# STC15_U1.net
KiCad netlist of a schematic drawn in Altium Designer
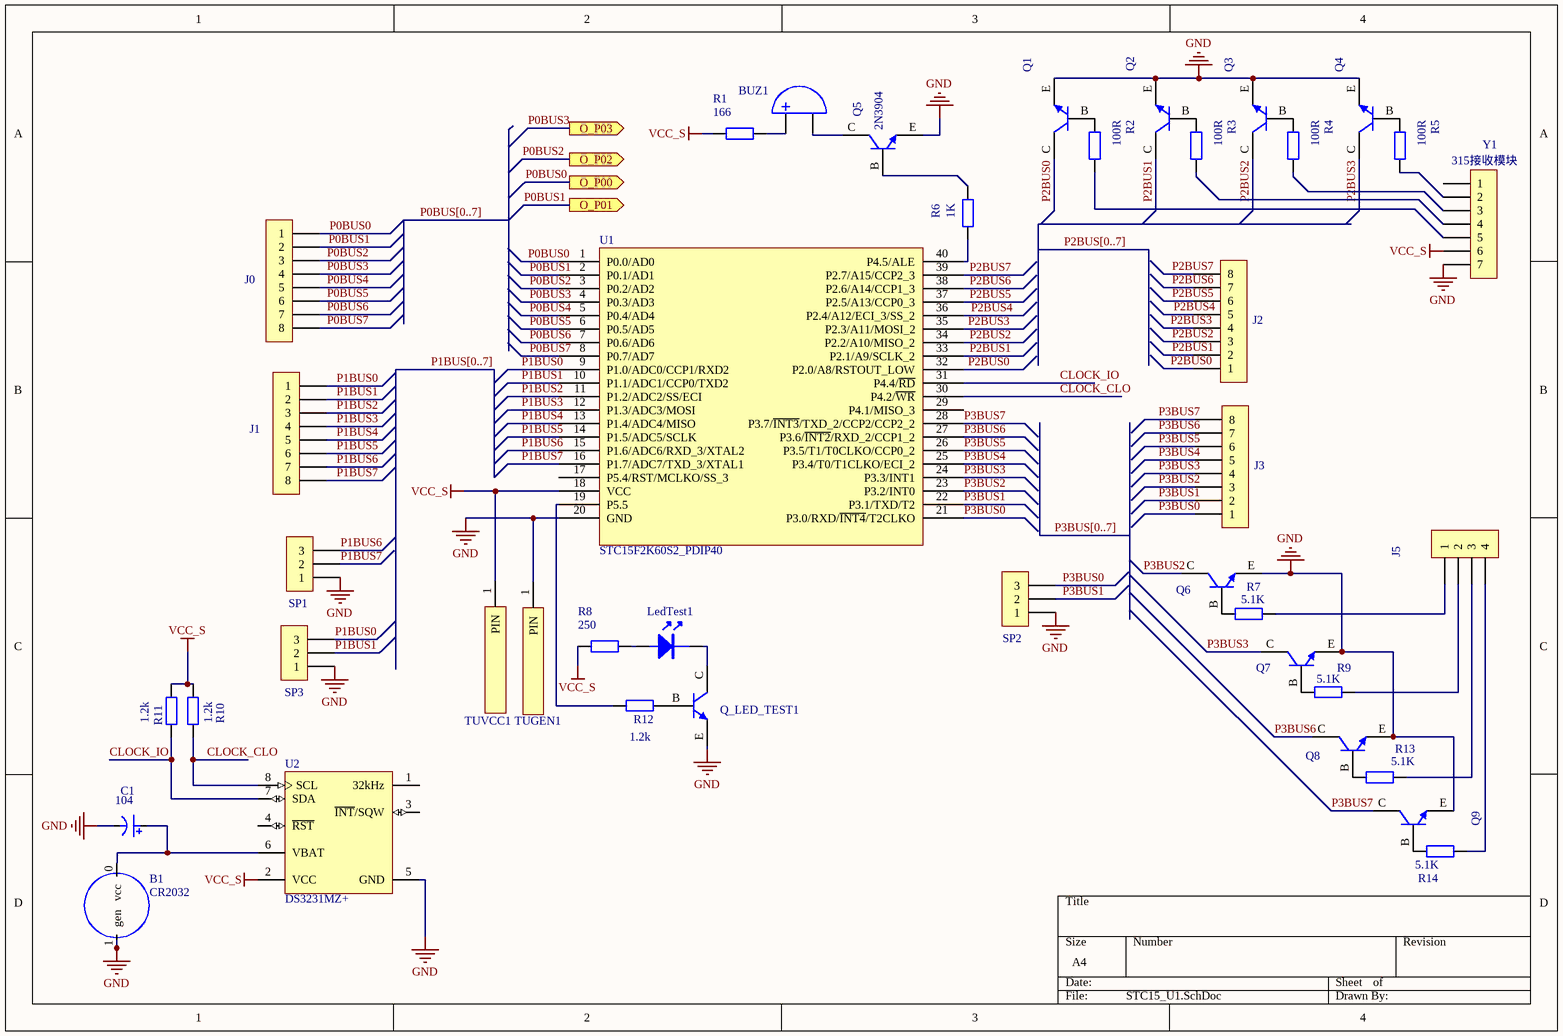
[diagram p0: STC15_U1.SchDoc]

(export (version "E")
  (design (tool "Eeschema 10.0.6"))
  (components
    (comp (ref "B1") (value "CR2032") (footprint "CR2032座") (libsource (lib "KF接口") (part "CR2032")))
    (comp (ref "BUZ1")
      (value "SD1209T5-A1")
      (footprint "BUZ5-12-0R5-9MM")
      (description "DIP,12x9mm,额定电压DC5V,频率2048Hz,黑色,间距5mm")
      (fields
        (field (name "PART NUMBER") "102BA-00004OD.01")
        (field (name "ALLOW ALTENATIVE PART") "Y")
        (field (name "REMARK") "Verified by BU1（黄雄青） check list V1.0")
        (field (name "MODIFY TIME") "2016年05月12号")
        (field (name "APPROVED") "YES")
      )
      (libsource (lib "IA-04") (part "Buzzer-2-P1"))
    )
    (comp (ref "C1")
      (value "104")
      (footprint "CE5-6R5X5-1mm")
      (description "DIP,电容量681pf,额定电压2000V,偏差±10%,6.5X5mm")
      (fields
        (field (name "PART NUMBER") "102CB-00002OD.01")
        (field (name "ALLOW ALTENATIVE PART") "Y")
        (field (name "REMARK") "Verified by BU1（黄雄青） check list V1.0")
        (field (name "MODIFY TIME") "2015年11月05号")
        (field (name "APPROVED") "YES")
      )
      (libsource (lib "IA-04") (part "CAP_Alum-2-N2"))
    )
    (comp (ref "J0")
      (value "W7810811120AB")
      (footprint "XH8P-2R54-TH")
      (description "DIP,座子,封装脚距2.54mm,180度,1x8PIN,塑高/针长7.0/3.40mm,白色")
      (fields
        (field (name "PART NUMBER") "102NB-00026CY.01")
        (field (name "ALLOW ALTENATIVE PART") "Y")
        (field (name "REMARK") "Verified by CRD（赖程奇） check list V1.0")
        (field (name "MODIFY TIME") "2016年08月22号")
        (field (name "APPROVED") "YES")
      )
      (libsource (lib "IA-04") (part "J-8-NP"))
    )
    (comp (ref "J1")
      (value "W7810811120AB")
      (footprint "XH8P-2R54-TH")
      (description "DIP,座子,封装脚距2.54mm,180度,1x8PIN,塑高/针长7.0/3.40mm,白色")
      (fields
        (field (name "PART NUMBER") "102NB-00026CY.01")
        (field (name "ALLOW ALTENATIVE PART") "Y")
        (field (name "REMARK") "Verified by CRD（赖程奇） check list V1.0")
        (field (name "MODIFY TIME") "2016年08月22号")
        (field (name "APPROVED") "YES")
      )
      (libsource (lib "IA-04") (part "J-8-NP"))
    )
    (comp (ref "J2")
      (value "W7810811120AB")
      (footprint "XH8P-2R54-TH")
      (description "DIP,座子,封装脚距2.54mm,180度,1x8PIN,塑高/针长7.0/3.40mm,白色")
      (fields
        (field (name "PART NUMBER") "102NB-00026CY.01")
        (field (name "ALLOW ALTENATIVE PART") "Y")
        (field (name "REMARK") "Verified by CRD（赖程奇） check list V1.0")
        (field (name "MODIFY TIME") "2016年08月22号")
        (field (name "APPROVED") "YES")
      )
      (libsource (lib "") (part "J-8-NP_1"))
    )
    (comp (ref "J3")
      (value "W7810811120AB")
      (footprint "XH8P-2R54-TH")
      (description "DIP,座子,封装脚距2.54mm,180度,1x8PIN,塑高/针长7.0/3.40mm,白色")
      (fields
        (field (name "PART NUMBER") "102NB-00026CY.01")
        (field (name "ALLOW ALTENATIVE PART") "Y")
        (field (name "REMARK") "Verified by CRD（赖程奇） check list V1.0")
        (field (name "MODIFY TIME") "2016年08月22号")
        (field (name "APPROVED") "YES")
      )
      (libsource (lib "") (part "J-8-NP_1"))
    )
    (comp (ref "J5")
      (value "W7810411120AB")
      (footprint "XH4P-2R54-TH")
      (description "DIP,座子,封装脚距2.54mm,180度,1x4PIN,塑高/针长7.0/3.40mm,白色")
      (fields
        (field (name "PART NUMBER") "102NB-00025CY.01")
        (field (name "ALLOW ALTENATIVE PART") "Y")
        (field (name "REMARK") "Verified by CRD（赖程奇） check list V1.0")
        (field (name "MODIFY TIME") "2016年05月12号")
        (field (name "APPROVED") "YES")
      )
      (libsource (lib "IA-04") (part "J-4-NP"))
    )
    (comp (ref "LedTest1")
      (value "333-2SUBD/S400-A4")
      (footprint "LED2-D5X5")
      (description "DIP,封装/间距直径5/2.54mm,额定电压3.3V,亮度高亮,蓝色")
      (fields
        (field (name "PART NUMBER") "102DL-00029CH.01")
        (field (name "ALLOW ALTENATIVE PART") "Y")
        (field (name "REMARK") "Verified by CRD（张宗良） check list V1.0")
        (field (name "MODIFY TIME") "2017年01月07号")
        (field (name "APPROVED") "YES")
      )
      (libsource (lib "IA-04") (part "Diode-LED-2-N2"))
    )
    (comp (ref "Q1")
      (value "2N3904")
      (footprint "Triode:TO-92-3-EBC")
      (description "DIP,封装形式TO-92-3,耐压值40V,额定电流200mA,耗散功率625mW")
      (fields
        (field (name "PART NUMBER") "102GN-00009BA.01")
        (field (name "ALLOW ALTENATIVE PART") "Y")
        (field (name "REMARK") "Verified by BU1（吴明徽）check list V1.0")
        (field (name "MODIFY TIME") "2015年08月08号")
        (field (name "APPROVED") "YES")
      )
      (libsource (lib "IA-04") (part "Triode-NPN-BCE"))
    )
    (comp (ref "Q2")
      (value "2N3904")
      (footprint "Triode:TO-92-3-EBC")
      (description "DIP,封装形式TO-92-3,耐压值40V,额定电流200mA,耗散功率625mW")
      (fields
        (field (name "PART NUMBER") "102GN-00009BA.01")
        (field (name "ALLOW ALTENATIVE PART") "Y")
        (field (name "REMARK") "Verified by BU1（吴明徽）check list V1.0")
        (field (name "MODIFY TIME") "2015年08月08号")
        (field (name "APPROVED") "YES")
      )
      (libsource (lib "IA-04") (part "Triode-NPN-BCE"))
    )
    (comp (ref "Q3")
      (value "2N3904")
      (footprint "Triode:TO-92-3-EBC")
      (description "DIP,封装形式TO-92-3,耐压值40V,额定电流200mA,耗散功率625mW")
      (fields
        (field (name "PART NUMBER") "102GN-00009BA.01")
        (field (name "ALLOW ALTENATIVE PART") "Y")
        (field (name "REMARK") "Verified by BU1（吴明徽）check list V1.0")
        (field (name "MODIFY TIME") "2015年08月08号")
        (field (name "APPROVED") "YES")
      )
      (libsource (lib "IA-04") (part "Triode-NPN-BCE"))
    )
    (comp (ref "Q4")
      (value "2N3904")
      (footprint "Triode:TO-92-3-EBC")
      (description "DIP,封装形式TO-92-3,耐压值40V,额定电流200mA,耗散功率625mW")
      (fields
        (field (name "PART NUMBER") "102GN-00009BA.01")
        (field (name "ALLOW ALTENATIVE PART") "Y")
        (field (name "REMARK") "Verified by BU1（吴明徽）check list V1.0")
        (field (name "MODIFY TIME") "2015年08月08号")
        (field (name "APPROVED") "YES")
      )
      (libsource (lib "IA-04") (part "Triode-NPN-BCE"))
    )
    (comp (ref "Q5")
      (value "2N3904")
      (footprint "Triode:TO-92-3-EBC")
      (description "DIP,封装形式TO-92-3,耐压值40V,额定电流200mA,耗散功率625mW")
      (fields
        (field (name "PART NUMBER") "102GN-00009BA.01")
        (field (name "ALLOW ALTENATIVE PART") "Y")
        (field (name "REMARK") "Verified by BU1（吴明徽）check list V1.0")
        (field (name "MODIFY TIME") "2015年08月08号")
        (field (name "APPROVED") "YES")
      )
      (libsource (lib "IA-04") (part "Triode-NPN-BCE"))
    )
    (comp (ref "Q6")
      (value "2N3904")
      (footprint "Triode:TO-92-3-EBC")
      (description "DIP,封装形式TO-92-3,耐压值40V,额定电流200mA,耗散功率625mW")
      (fields
        (field (name "PART NUMBER") "102GN-00009BA.01")
        (field (name "ALLOW ALTENATIVE PART") "Y")
        (field (name "REMARK") "Verified by BU1（吴明徽）check list V1.0")
        (field (name "MODIFY TIME") "2015年08月08号")
        (field (name "APPROVED") "YES")
      )
      (libsource (lib "IA-04") (part "Triode-NPN-BCE"))
    )
    (comp (ref "Q7")
      (value "2N3904")
      (footprint "Triode:TO-92-3-EBC")
      (description "DIP,封装形式TO-92-3,耐压值40V,额定电流200mA,耗散功率625mW")
      (fields
        (field (name "PART NUMBER") "102GN-00009BA.01")
        (field (name "ALLOW ALTENATIVE PART") "Y")
        (field (name "REMARK") "Verified by BU1（吴明徽）check list V1.0")
        (field (name "MODIFY TIME") "2015年08月08号")
        (field (name "APPROVED") "YES")
      )
      (libsource (lib "IA-04") (part "Triode-NPN-BCE"))
    )
    (comp (ref "Q8")
      (value "2N3904")
      (footprint "Triode:TO-92-3-EBC")
      (description "DIP,封装形式TO-92-3,耐压值40V,额定电流200mA,耗散功率625mW")
      (fields
        (field (name "PART NUMBER") "102GN-00009BA.01")
        (field (name "ALLOW ALTENATIVE PART") "Y")
        (field (name "REMARK") "Verified by BU1（吴明徽）check list V1.0")
        (field (name "MODIFY TIME") "2015年08月08号")
        (field (name "APPROVED") "YES")
      )
      (libsource (lib "IA-04") (part "Triode-NPN-BCE"))
    )
    (comp (ref "Q9")
      (value "2N3904")
      (footprint "Triode:TO-92-3-EBC")
      (description "DIP,封装形式TO-92-3,耐压值40V,额定电流200mA,耗散功率625mW")
      (fields
        (field (name "PART NUMBER") "102GN-00009BA.01")
        (field (name "ALLOW ALTENATIVE PART") "Y")
        (field (name "REMARK") "Verified by BU1（吴明徽）check list V1.0")
        (field (name "MODIFY TIME") "2015年08月08号")
        (field (name "APPROVED") "YES")
      )
      (libsource (lib "IA-04") (part "Triode-NPN-BCE"))
    )
    (comp (ref "Q_LED_TEST1")
      (value "2N3904")
      (footprint "Triode:TO-92-3-EBC")
      (description "DIP,封装形式TO-92-3,耐压值40V,额定电流200mA,耗散功率625mW")
      (fields
        (field (name "PART NUMBER") "102GN-00009BA.01")
        (field (name "ALLOW ALTENATIVE PART") "Y")
        (field (name "REMARK") "Verified by BU1（吴明徽）check list V1.0")
        (field (name "MODIFY TIME") "2015年08月08号")
        (field (name "APPROVED") "YES")
      )
      (libsource (lib "IA-04") (part "Triode-NPN-BCE"))
    )
    (comp (ref "R1")
      (value "166")
      (footprint "RY0R25W")
      (description "DIP,阻值1K,精度±5%,9.0x3.3mm,额定功率1/2W")
      (fields
        (field (name "PART NUMBER") "102RO-00079BW.01")
        (field (name "ALLOW ALTENATIVE PART") "Y")
        (field (name "REMARK") "Verified by BU3（吴明徽）check list V1.0")
        (field (name "MODIFY TIME") "2015年07月10号")
        (field (name "APPROVED") "YES")
      )
      (libsource (lib "") (part "RES-2-NP_1"))
    )
    (comp (ref "R2")
      (value "100R")
      (footprint "RY0R25W")
      (description "DIP,阻值100R,精度±1%,6.1x2.29mm,额定功率1/4W")
      (fields
        (field (name "PART NUMBER") "102RO-00040BS.01")
        (field (name "ALLOW ALTENATIVE PART") "Y")
        (field (name "REMARK") "Verified by BU3（吴明徽）check list V1.0")
        (field (name "MODIFY TIME") "2015年07月10号")
        (field (name "APPROVED") "YES")
      )
      (libsource (lib "IA-04") (part "RES-2-NP"))
    )
    (comp (ref "R3")
      (value "100R")
      (footprint "RY0R25W")
      (description "DIP,阻值100R,精度±1%,6.1x2.29mm,额定功率1/4W")
      (fields
        (field (name "PART NUMBER") "102RO-00040BS.01")
        (field (name "ALLOW ALTENATIVE PART") "Y")
        (field (name "REMARK") "Verified by BU3（吴明徽）check list V1.0")
        (field (name "MODIFY TIME") "2015年07月10号")
        (field (name "APPROVED") "YES")
      )
      (libsource (lib "IA-04") (part "RES-2-NP"))
    )
    (comp (ref "R4")
      (value "100R")
      (footprint "RY0R25W")
      (description "DIP,阻值100R,精度±1%,6.1x2.29mm,额定功率1/4W")
      (fields
        (field (name "PART NUMBER") "102RO-00040BS.01")
        (field (name "ALLOW ALTENATIVE PART") "Y")
        (field (name "REMARK") "Verified by BU3（吴明徽）check list V1.0")
        (field (name "MODIFY TIME") "2015年07月10号")
        (field (name "APPROVED") "YES")
      )
      (libsource (lib "IA-04") (part "RES-2-NP"))
    )
    (comp (ref "R5")
      (value "100R")
      (footprint "RY0R25W")
      (description "DIP,阻值100R,精度±1%,6.1x2.29mm,额定功率1/4W")
      (fields
        (field (name "PART NUMBER") "102RO-00040BS.01")
        (field (name "ALLOW ALTENATIVE PART") "Y")
        (field (name "REMARK") "Verified by BU3（吴明徽）check list V1.0")
        (field (name "MODIFY TIME") "2015年07月10号")
        (field (name "APPROVED") "YES")
      )
      (libsource (lib "IA-04") (part "RES-2-NP"))
    )
    (comp (ref "R6")
      (value "1K")
      (footprint "RY0R25W")
      (description "DIP,阻值1K,精度±5%,9.0x3.3mm,额定功率1/2W")
      (fields
        (field (name "PART NUMBER") "102RO-00079BW.01")
        (field (name "ALLOW ALTENATIVE PART") "Y")
        (field (name "REMARK") "Verified by BU3（吴明徽）check list V1.0")
        (field (name "MODIFY TIME") "2015年07月10号")
        (field (name "APPROVED") "YES")
      )
      (libsource (lib "") (part "RES-2-NP_2"))
    )
    (comp (ref "R7")
      (value "5.1K")
      (footprint "RY0R25W")
      (description "DIP,阻值5.1K,精度±1%,6.2x2.29mm,额定功率1/4W")
      (fields
        (field (name "PART NUMBER") "102RO-00048BS.01")
        (field (name "ALLOW ALTENATIVE PART") "Y")
        (field (name "REMARK") "Verified by BU3（吴明徽）check list V1.0")
        (field (name "MODIFY TIME") "2015年07月10号")
        (field (name "APPROVED") "YES")
      )
      (libsource (lib "") (part "RES-2-NP_1"))
    )
    (comp (ref "R8")
      (value "250")
      (footprint "RY0R25W")
      (description "DIP,阻值8.2R,精度±1%,AXIAL0.4,额定功率1/2W")
      (fields
        (field (name "PART NUMBER") "102RO-00036BS.01")
        (field (name "ALLOW ALTENATIVE PART") "Y")
        (field (name "REMARK") "Verified by BU3（吴明徽）check list V1.0")
        (field (name "MODIFY TIME") "2015年07月10号")
        (field (name "APPROVED") "YES")
      )
      (libsource (lib "") (part "RES-2-NP_1"))
    )
    (comp (ref "R9")
      (value "5.1K")
      (footprint "RY0R25W")
      (description "DIP,阻值5.1K,精度±1%,6.2x2.29mm,额定功率1/4W")
      (fields
        (field (name "PART NUMBER") "102RO-00048BS.01")
        (field (name "ALLOW ALTENATIVE PART") "Y")
        (field (name "REMARK") "Verified by BU3（吴明徽）check list V1.0")
        (field (name "MODIFY TIME") "2015年07月10号")
        (field (name "APPROVED") "YES")
      )
      (libsource (lib "") (part "RES-2-NP_1"))
    )
    (comp (ref "R10")
      (value "1.2k")
      (footprint "RY0R25W")
      (description "DIP,阻值8.2R,精度±1%,AXIAL0.4,额定功率1/2W")
      (fields
        (field (name "PART NUMBER") "102RO-00036BS.01")
        (field (name "ALLOW ALTENATIVE PART") "Y")
        (field (name "REMARK") "Verified by BU3（吴明徽）check list V1.0")
        (field (name "MODIFY TIME") "2015年07月10号")
        (field (name "APPROVED") "YES")
      )
      (libsource (lib "IA-04") (part "RES-2-NP"))
    )
    (comp (ref "R11")
      (value "1.2k")
      (footprint "RY0R25W")
      (description "DIP,阻值8.2R,精度±1%,AXIAL0.4,额定功率1/2W")
      (fields
        (field (name "PART NUMBER") "102RO-00036BS.01")
        (field (name "ALLOW ALTENATIVE PART") "Y")
        (field (name "REMARK") "Verified by BU3（吴明徽）check list V1.0")
        (field (name "MODIFY TIME") "2015年07月10号")
        (field (name "APPROVED") "YES")
      )
      (libsource (lib "IA-04") (part "RES-2-NP"))
    )
    (comp (ref "R12")
      (value "1.2k")
      (footprint "RY0R25W")
      (description "DIP,阻值8.2R,精度±1%,AXIAL0.4,额定功率1/2W")
      (fields
        (field (name "PART NUMBER") "102RO-00036BS.01")
        (field (name "ALLOW ALTENATIVE PART") "Y")
        (field (name "REMARK") "Verified by BU3（吴明徽）check list V1.0")
        (field (name "MODIFY TIME") "2015年07月10号")
        (field (name "APPROVED") "YES")
      )
      (libsource (lib "") (part "RES-2-NP_1"))
    )
    (comp (ref "R13")
      (value "5.1K")
      (footprint "RY0R25W")
      (description "DIP,阻值5.1K,精度±1%,6.2x2.29mm,额定功率1/4W")
      (fields
        (field (name "PART NUMBER") "102RO-00048BS.01")
        (field (name "ALLOW ALTENATIVE PART") "Y")
        (field (name "REMARK") "Verified by BU3（吴明徽）check list V1.0")
        (field (name "MODIFY TIME") "2015年07月10号")
        (field (name "APPROVED") "YES")
      )
      (libsource (lib "") (part "RES-2-NP_1"))
    )
    (comp (ref "R14")
      (value "5.1K")
      (footprint "RY0R25W")
      (description "DIP,阻值5.1K,精度±1%,6.2x2.29mm,额定功率1/4W")
      (fields
        (field (name "PART NUMBER") "102RO-00048BS.01")
        (field (name "ALLOW ALTENATIVE PART") "Y")
        (field (name "REMARK") "Verified by BU3（吴明徽）check list V1.0")
        (field (name "MODIFY TIME") "2015年07月10号")
        (field (name "APPROVED") "YES")
      )
      (libsource (lib "") (part "RES-2-NP_1"))
    )
    (comp (ref "SP1")
      (value "~")
      (footprint "XH3P-2R54-TH")
      (description "DIP,座子,封装脚距2.54mm,180度,1x3PIN,塑高/针长7.0/3.40mm,白色")
      (fields
        (field (name "PART NUMBER") "102NB-00017CY.01")
        (field (name "ALLOW ALTENATIVE PART") "Y")
        (field (name "REMARK") "Verified by CRD（赖程奇） check list V1.0")
        (field (name "MODIFY TIME") "2015年11月06号")
        (field (name "APPROVED") "YES")
      )
      (libsource (lib "IA-04") (part "J-3-NP"))
    )
    (comp (ref "SP2")
      (value "~")
      (footprint "XH3P-2R54-TH")
      (description "DIP,座子,封装脚距2.54mm,180度,1x3PIN,塑高/针长7.0/3.40mm,白色")
      (fields
        (field (name "PART NUMBER") "102NB-00017CY.01")
        (field (name "ALLOW ALTENATIVE PART") "Y")
        (field (name "REMARK") "Verified by CRD（赖程奇） check list V1.0")
        (field (name "MODIFY TIME") "2015年11月06号")
        (field (name "APPROVED") "YES")
      )
      (libsource (lib "IA-04") (part "J-3-NP"))
    )
    (comp (ref "SP3")
      (value "~")
      (footprint "XH3P-2R54-TH")
      (description "DIP,座子,封装脚距2.54mm,180度,1x3PIN,塑高/针长7.0/3.40mm,白色")
      (fields
        (field (name "PART NUMBER") "102NB-00017CY.01")
        (field (name "ALLOW ALTENATIVE PART") "Y")
        (field (name "REMARK") "Verified by CRD（赖程奇） check list V1.0")
        (field (name "MODIFY TIME") "2015年11月06号")
        (field (name "APPROVED") "YES")
      )
      (libsource (lib "IA-04") (part "J-3-NP"))
    )
    (comp (ref "TUGEN1")
      (value "T？")
      (footprint "铺铜条")
      (description "2mm*20的铜条用于焊接")
      (libsource (lib "KF接口") (part "铺铜条"))
    )
    (comp (ref "TUVCC1")
      (value "T？")
      (footprint "铺铜条")
      (description "2mm*20的铜条用于焊接")
      (libsource (lib "KF接口") (part "铺铜条"))
    )
    (comp (ref "U1")
      (value "STC15F2K60S2_PDIP40")
      (footprint "DIP40")
      (libsource (lib "stcmcu_altium1819") (part "STC15F2K60S2_PDIP40"))
    )
    (comp (ref "U2")
      (value "DS3231MZ+")
      (footprint "S8MK+1_L")
      (description "+/-5ppm, MEMS based Real-Time Clock, I2C Interface, 8-Pin SO, -40 to 85 degC, Pb-Free")
      (libsource (lib "Maxim Real-Time Clocks (RTCs)") (part "DS3231MZ+"))
    )
    (comp (ref "Y1")
      (value "315接收模块")
      (footprint "CON7P-2R54-TH")
      (description "DIP,封装脚距2.54mm,180度,1x7PIN,黑色")
      (fields
        (field (name "PART NUMBER") "102NL-00032BV.01")
        (field (name "ALLOW ALTENATIVE PART") "Y")
        (field (name "REMARK") "Verified by CRD（赖程奇） check list V1.0")
        (field (name "MODIFY TIME") "2015年07月10号")
        (field (name "APPROVED") "YES")
      )
      (libsource (lib "IA-04") (part "CON7-NP"))
    )
  )
  (nets
    (net (code "1") (name "/CLOCK_CLO") (class "Default")
      (node (ref "R10") (pin "2") (pinfunction "2_2") (pintype "passive"))
      (node (ref "U1") (pin "30") (pinfunction "P4.2/~{WR}_30") (pintype "passive"))
      (node (ref "U2") (pin "8") (pinfunction "SCL_8") (pintype "input"))
    )
    (net (code "2") (name "/CLOCK_IO") (class "Default")
      (node (ref "R11") (pin "2") (pinfunction "2_2") (pintype "passive"))
      (node (ref "U1") (pin "31") (pinfunction "P4.4/~{RD}_31") (pintype "passive"))
      (node (ref "U2") (pin "7") (pinfunction "SDA_7") (pintype "bidirectional"))
    )
    (net (code "3") (name "/P0BUS0") (class "Default")
      (node (ref "J0") (pin "1") (pinfunction "1_1") (pintype "passive"))
      (node (ref "U1") (pin "1") (pinfunction "P0.0/AD0_1") (pintype "passive"))
    )
    (net (code "4") (name "/P0BUS1") (class "Default")
      (node (ref "J0") (pin "2") (pinfunction "2_2") (pintype "passive"))
      (node (ref "U1") (pin "2") (pinfunction "P0.1/AD1_2") (pintype "passive"))
    )
    (net (code "5") (name "/P0BUS2") (class "Default")
      (node (ref "J0") (pin "3") (pinfunction "3_3") (pintype "passive"))
      (node (ref "U1") (pin "3") (pinfunction "P0.2/AD2_3") (pintype "passive"))
    )
    (net (code "6") (name "/P0BUS3") (class "Default")
      (node (ref "J0") (pin "4") (pinfunction "4_4") (pintype "passive"))
      (node (ref "U1") (pin "4") (pinfunction "P0.3/AD3_4") (pintype "passive"))
    )
    (net (code "7") (name "/P0BUS4") (class "Default")
      (node (ref "J0") (pin "5") (pinfunction "5_5") (pintype "passive"))
      (node (ref "U1") (pin "5") (pinfunction "P0.4/AD4_5") (pintype "passive"))
    )
    (net (code "8") (name "/P0BUS5") (class "Default")
      (node (ref "J0") (pin "6") (pinfunction "6_6") (pintype "passive"))
      (node (ref "U1") (pin "6") (pinfunction "P0.5/AD5_6") (pintype "passive"))
    )
    (net (code "9") (name "/P0BUS6") (class "Default")
      (node (ref "J0") (pin "7") (pinfunction "7_7") (pintype "passive"))
      (node (ref "U1") (pin "7") (pinfunction "P0.6/AD6_7") (pintype "passive"))
    )
    (net (code "10") (name "/P0BUS7") (class "Default")
      (node (ref "J0") (pin "8") (pinfunction "8_8") (pintype "passive"))
      (node (ref "U1") (pin "8") (pinfunction "P0.7/AD7_8") (pintype "passive"))
    )
    (net (code "12") (name "/P1BUS0") (class "Default")
      (node (ref "J1") (pin "1") (pinfunction "1_1") (pintype "passive"))
      (node (ref "SP3") (pin "3") (pinfunction "3_3") (pintype "passive"))
      (node (ref "U1") (pin "9") (pinfunction "P1.0/ADC0/CCP1/RXD2_9") (pintype "passive"))
    )
    (net (code "13") (name "/P1BUS1") (class "Default")
      (node (ref "J1") (pin "2") (pinfunction "2_2") (pintype "passive"))
      (node (ref "SP3") (pin "2") (pinfunction "2_2") (pintype "passive"))
      (node (ref "U1") (pin "10") (pinfunction "P1.1/ADC1/CCP0/TXD2_10") (pintype "passive"))
    )
    (net (code "14") (name "/P1BUS2") (class "Default")
      (node (ref "J1") (pin "3") (pinfunction "3_3") (pintype "passive"))
      (node (ref "U1") (pin "11") (pinfunction "P1.2/ADC2/SS/ECI_11") (pintype "passive"))
    )
    (net (code "15") (name "/P1BUS3") (class "Default")
      (node (ref "J1") (pin "4") (pinfunction "4_4") (pintype "passive"))
      (node (ref "U1") (pin "12") (pinfunction "P1.3/ADC3/MOSI_12") (pintype "passive"))
    )
    (net (code "16") (name "/P1BUS4") (class "Default")
      (node (ref "J1") (pin "5") (pinfunction "5_5") (pintype "passive"))
      (node (ref "U1") (pin "13") (pinfunction "P1.4/ADC4/MISO_13") (pintype "passive"))
    )
    (net (code "17") (name "/P1BUS5") (class "Default")
      (node (ref "J1") (pin "6") (pinfunction "6_6") (pintype "passive"))
      (node (ref "U1") (pin "14") (pinfunction "P1.5/ADC5/SCLK_14") (pintype "passive"))
    )
    (net (code "18") (name "/P1BUS6") (class "Default")
      (node (ref "J1") (pin "7") (pinfunction "7_7") (pintype "passive"))
      (node (ref "SP1") (pin "3") (pinfunction "3_3") (pintype "passive"))
      (node (ref "U1") (pin "15") (pinfunction "P1.6/ADC6/RXD_3/XTAL2_15") (pintype "passive"))
    )
    (net (code "19") (name "/P1BUS7") (class "Default")
      (node (ref "J1") (pin "8") (pinfunction "8_8") (pintype "passive"))
      (node (ref "SP1") (pin "2") (pinfunction "2_2") (pintype "passive"))
      (node (ref "U1") (pin "16") (pinfunction "P1.7/ADC7/TXD_3/XTAL1_16") (pintype "passive"))
    )
    (net (code "21") (name "/P2BUS0") (class "Default")
      (node (ref "J2") (pin "1") (pinfunction "1_1") (pintype "passive"))
      (node (ref "Q1") (pin "C") (pinfunction "C_C") (pintype "passive"))
      (node (ref "U1") (pin "32") (pinfunction "P2.0/A8/RSTOUT_LOW_32") (pintype "passive"))
    )
    (net (code "22") (name "/P2BUS1") (class "Default")
      (node (ref "J2") (pin "2") (pinfunction "2_2") (pintype "passive"))
      (node (ref "Q2") (pin "C") (pinfunction "C_C") (pintype "passive"))
      (node (ref "U1") (pin "33") (pinfunction "P2.1/A9/SCLK_2_33") (pintype "passive"))
    )
    (net (code "23") (name "/P2BUS2") (class "Default")
      (node (ref "J2") (pin "3") (pinfunction "3_3") (pintype "passive"))
      (node (ref "Q3") (pin "C") (pinfunction "C_C") (pintype "passive"))
      (node (ref "U1") (pin "34") (pinfunction "P2.2/A10/MISO_2_34") (pintype "passive"))
    )
    (net (code "24") (name "/P2BUS3") (class "Default")
      (node (ref "J2") (pin "4") (pinfunction "4_4") (pintype "passive"))
      (node (ref "Q4") (pin "C") (pinfunction "C_C") (pintype "passive"))
      (node (ref "U1") (pin "35") (pinfunction "P2.3/A11/MOSI_2_35") (pintype "passive"))
    )
    (net (code "25") (name "/P2BUS4") (class "Default")
      (node (ref "J2") (pin "5") (pinfunction "5_5") (pintype "passive"))
      (node (ref "U1") (pin "36") (pinfunction "P2.4/A12/ECI_3/SS_2_36") (pintype "passive"))
    )
    (net (code "26") (name "/P2BUS5") (class "Default")
      (node (ref "J2") (pin "6") (pinfunction "6_6") (pintype "passive"))
      (node (ref "U1") (pin "37") (pinfunction "P2.5/A13/CCP0_3_37") (pintype "passive"))
    )
    (net (code "27") (name "/P2BUS6") (class "Default")
      (node (ref "J2") (pin "7") (pinfunction "7_7") (pintype "passive"))
      (node (ref "U1") (pin "38") (pinfunction "P2.6/A14/CCP1_3_38") (pintype "passive"))
    )
    (net (code "28") (name "/P2BUS7") (class "Default")
      (node (ref "J2") (pin "8") (pinfunction "8_8") (pintype "passive"))
      (node (ref "U1") (pin "39") (pinfunction "P2.7/A15/CCP2_3_39") (pintype "passive"))
    )
    (net (code "30") (name "/P3BUS0") (class "Default")
      (node (ref "J3") (pin "1") (pinfunction "1_1") (pintype "passive"))
      (node (ref "SP2") (pin "3") (pinfunction "3_3") (pintype "passive"))
      (node (ref "U1") (pin "21") (pinfunction "P3.0/RXD/~{INT4}/T2CLKO_21") (pintype "passive"))
    )
    (net (code "31") (name "/P3BUS1") (class "Default")
      (node (ref "J3") (pin "2") (pinfunction "2_2") (pintype "passive"))
      (node (ref "SP2") (pin "2") (pinfunction "2_2") (pintype "passive"))
      (node (ref "U1") (pin "22") (pinfunction "P3.1/TXD/T2_22") (pintype "passive"))
    )
    (net (code "32") (name "/P3BUS2") (class "Default")
      (node (ref "J3") (pin "3") (pinfunction "3_3") (pintype "passive"))
      (node (ref "Q6") (pin "C") (pinfunction "C_C") (pintype "passive"))
      (node (ref "U1") (pin "23") (pinfunction "P3.2/INT0_23") (pintype "passive"))
    )
    (net (code "33") (name "/P3BUS3") (class "Default")
      (node (ref "J3") (pin "4") (pinfunction "4_4") (pintype "passive"))
      (node (ref "Q7") (pin "C") (pinfunction "C_C") (pintype "passive"))
      (node (ref "U1") (pin "24") (pinfunction "P3.3/INT1_24") (pintype "passive"))
    )
    (net (code "34") (name "/P3BUS4") (class "Default")
      (node (ref "J3") (pin "5") (pinfunction "5_5") (pintype "passive"))
      (node (ref "U1") (pin "25") (pinfunction "P3.4/T0/T1CLKO/ECI_2_25") (pintype "passive"))
    )
    (net (code "35") (name "/P3BUS5") (class "Default")
      (node (ref "J3") (pin "6") (pinfunction "6_6") (pintype "passive"))
      (node (ref "U1") (pin "26") (pinfunction "P3.5/T1/T0CLKO/CCP0_2_26") (pintype "passive"))
    )
    (net (code "36") (name "/P3BUS6") (class "Default")
      (node (ref "J3") (pin "7") (pinfunction "7_7") (pintype "passive"))
      (node (ref "Q8") (pin "C") (pinfunction "C_C") (pintype "passive"))
      (node (ref "U1") (pin "27") (pinfunction "P3.6/~{INT2}/RXD_2/CCP1_2_27") (pintype "passive"))
    )
    (net (code "37") (name "/P3BUS7") (class "Default")
      (node (ref "J3") (pin "8") (pinfunction "8_8") (pintype "passive"))
      (node (ref "Q9") (pin "C") (pinfunction "C_C") (pintype "passive"))
      (node (ref "U1") (pin "28") (pinfunction "P3.7/~{INT3}/TXD_2/CCP2/CCP2_2_28") (pintype "passive"))
    )
    (net (code "39") (name "GND") (class "Default")
      (node (ref "B1") (pin "1") (pinfunction "gen_1") (pintype "passive"))
      (node (ref "C1") (pin "2") (pinfunction "2_2") (pintype "passive"))
      (node (ref "Q1") (pin "E") (pinfunction "E_E") (pintype "passive"))
      (node (ref "Q2") (pin "E") (pinfunction "E_E") (pintype "passive"))
      (node (ref "Q3") (pin "E") (pinfunction "E_E") (pintype "passive"))
      (node (ref "Q4") (pin "E") (pinfunction "E_E") (pintype "passive"))
      (node (ref "Q5") (pin "E") (pinfunction "E_E") (pintype "passive"))
      (node (ref "Q6") (pin "E") (pinfunction "E_E") (pintype "passive"))
      (node (ref "Q7") (pin "E") (pinfunction "E_E") (pintype "passive"))
      (node (ref "Q8") (pin "E") (pinfunction "E_E") (pintype "passive"))
      (node (ref "Q9") (pin "E") (pinfunction "E_E") (pintype "passive"))
      (node (ref "Q_LED_TEST1") (pin "E") (pinfunction "E_E") (pintype "passive"))
      (node (ref "SP1") (pin "1") (pinfunction "1_1") (pintype "passive"))
      (node (ref "SP2") (pin "1") (pinfunction "1_1") (pintype "passive"))
      (node (ref "SP3") (pin "1") (pinfunction "1_1") (pintype "passive"))
      (node (ref "TUGEN1") (pin "1") (pinfunction "PIN_1") (pintype "passive"))
      (node (ref "U1") (pin "20") (pinfunction "GND_20") (pintype "passive"))
      (node (ref "U2") (pin "5") (pinfunction "GND_5") (pintype "power_in"))
      (node (ref "Y1") (pin "7") (pinfunction "7_7") (pintype "passive"))
    )
    (net (code "40") (name "Net-(B1-vcc)") (class "Default")
      (node (ref "B1") (pin "0") (pinfunction "vcc_0") (pintype "passive"))
      (node (ref "C1") (pin "1") (pinfunction "1_1") (pintype "passive"))
      (node (ref "U2") (pin "6") (pinfunction "VBAT_6") (pintype "power_in"))
    )
    (net (code "41") (name "Net-(BUZ1-Pad1)") (class "Default")
      (node (ref "BUZ1") (pin "1") (pinfunction "1_1") (pintype "passive"))
      (node (ref "R1") (pin "2") (pinfunction "2_2") (pintype "passive"))
    )
    (net (code "42") (name "Net-(BUZ1-Pad2)") (class "Default")
      (node (ref "BUZ1") (pin "2") (pinfunction "2_2") (pintype "passive"))
      (node (ref "Q5") (pin "C") (pinfunction "C_C") (pintype "passive"))
    )
    (net (code "43") (name "Net-(J5-Pad1)") (class "Default")
      (node (ref "J5") (pin "1") (pinfunction "1_1") (pintype "passive"))
      (node (ref "R7") (pin "2") (pinfunction "2_2") (pintype "passive"))
    )
    (net (code "44") (name "Net-(J5-Pad2)") (class "Default")
      (node (ref "J5") (pin "2") (pinfunction "2_2") (pintype "passive"))
      (node (ref "R9") (pin "2") (pinfunction "2_2") (pintype "passive"))
    )
    (net (code "45") (name "Net-(J5-Pad3)") (class "Default")
      (node (ref "J5") (pin "3") (pinfunction "3_3") (pintype "passive"))
      (node (ref "R13") (pin "2") (pinfunction "2_2") (pintype "passive"))
    )
    (net (code "46") (name "Net-(J5-Pad4)") (class "Default")
      (node (ref "J5") (pin "4") (pinfunction "4_4") (pintype "passive"))
      (node (ref "R14") (pin "2") (pinfunction "2_2") (pintype "passive"))
    )
    (net (code "47") (name "Net-(LedTest1-Pad1)") (class "Default")
      (node (ref "LedTest1") (pin "1") (pinfunction "1_1") (pintype "passive"))
      (node (ref "R8") (pin "2") (pinfunction "2_2") (pintype "passive"))
    )
    (net (code "48") (name "Net-(LedTest1-Pad2)") (class "Default")
      (node (ref "LedTest1") (pin "2") (pinfunction "2_2") (pintype "passive"))
      (node (ref "Q_LED_TEST1") (pin "C") (pinfunction "C_C") (pintype "passive"))
    )
    (net (code "49") (name "Net-(Q1-PadB)") (class "Default")
      (node (ref "Q1") (pin "B") (pinfunction "B_B") (pintype "passive"))
      (node (ref "R2") (pin "1") (pinfunction "1_1") (pintype "passive"))
    )
    (net (code "50") (name "Net-(Q2-PadB)") (class "Default")
      (node (ref "Q2") (pin "B") (pinfunction "B_B") (pintype "passive"))
      (node (ref "R3") (pin "1") (pinfunction "1_1") (pintype "passive"))
    )
    (net (code "51") (name "Net-(Q3-PadB)") (class "Default")
      (node (ref "Q3") (pin "B") (pinfunction "B_B") (pintype "passive"))
      (node (ref "R4") (pin "1") (pinfunction "1_1") (pintype "passive"))
    )
    (net (code "52") (name "Net-(Q4-PadB)") (class "Default")
      (node (ref "Q4") (pin "B") (pinfunction "B_B") (pintype "passive"))
      (node (ref "R5") (pin "1") (pinfunction "1_1") (pintype "passive"))
    )
    (net (code "53") (name "Net-(Q5-PadB)") (class "Default")
      (node (ref "Q5") (pin "B") (pinfunction "B_B") (pintype "passive"))
      (node (ref "R6") (pin "2") (pinfunction "2_2") (pintype "passive"))
    )
    (net (code "54") (name "Net-(Q6-PadB)") (class "Default")
      (node (ref "Q6") (pin "B") (pinfunction "B_B") (pintype "passive"))
      (node (ref "R7") (pin "1") (pinfunction "1_1") (pintype "passive"))
    )
    (net (code "55") (name "Net-(Q7-PadB)") (class "Default")
      (node (ref "Q7") (pin "B") (pinfunction "B_B") (pintype "passive"))
      (node (ref "R9") (pin "1") (pinfunction "1_1") (pintype "passive"))
    )
    (net (code "56") (name "Net-(Q8-PadB)") (class "Default")
      (node (ref "Q8") (pin "B") (pinfunction "B_B") (pintype "passive"))
      (node (ref "R13") (pin "1") (pinfunction "1_1") (pintype "passive"))
    )
    (net (code "57") (name "Net-(Q9-PadB)") (class "Default")
      (node (ref "Q9") (pin "B") (pinfunction "B_B") (pintype "passive"))
      (node (ref "R14") (pin "1") (pinfunction "1_1") (pintype "passive"))
    )
    (net (code "58") (name "Net-(Q_LED_TEST1-PadB)") (class "Default")
      (node (ref "Q_LED_TEST1") (pin "B") (pinfunction "B_B") (pintype "passive"))
      (node (ref "R12") (pin "2") (pinfunction "2_2") (pintype "passive"))
    )
    (net (code "59") (name "Net-(R2-Pad2)") (class "Default")
      (node (ref "R2") (pin "2") (pinfunction "2_2") (pintype "passive"))
      (node (ref "Y1") (pin "5") (pinfunction "5_5") (pintype "passive"))
    )
    (net (code "60") (name "Net-(R3-Pad2)") (class "Default")
      (node (ref "R3") (pin "2") (pinfunction "2_2") (pintype "passive"))
      (node (ref "Y1") (pin "4") (pinfunction "4_4") (pintype "passive"))
    )
    (net (code "61") (name "Net-(R4-Pad2)") (class "Default")
      (node (ref "R4") (pin "2") (pinfunction "2_2") (pintype "passive"))
      (node (ref "Y1") (pin "3") (pinfunction "3_3") (pintype "passive"))
    )
    (net (code "62") (name "Net-(R5-Pad2)") (class "Default")
      (node (ref "R5") (pin "2") (pinfunction "2_2") (pintype "passive"))
      (node (ref "Y1") (pin "2") (pinfunction "2_2") (pintype "passive"))
    )
    (net (code "63") (name "Net-(U1-P4.5{slash}ALE)") (class "Default")
      (node (ref "R6") (pin "1") (pinfunction "1_1") (pintype "passive"))
      (node (ref "U1") (pin "40") (pinfunction "P4.5/ALE_40") (pintype "passive"))
    )
    (net (code "64") (name "Net-(U1-P5.5)") (class "Default")
      (node (ref "R12") (pin "1") (pinfunction "1_1") (pintype "passive"))
      (node (ref "U1") (pin "19") (pinfunction "P5.5_19") (pintype "passive"))
    )
    (net (code "65") (name "VCC_S") (class "Default")
      (node (ref "R1") (pin "1") (pinfunction "1_1") (pintype "passive"))
      (node (ref "R10") (pin "1") (pinfunction "1_1") (pintype "passive"))
      (node (ref "R11") (pin "1") (pinfunction "1_1") (pintype "passive"))
      (node (ref "R8") (pin "1") (pinfunction "1_1") (pintype "passive"))
      (node (ref "TUVCC1") (pin "1") (pinfunction "PIN_1") (pintype "passive"))
      (node (ref "U1") (pin "18") (pinfunction "VCC_18") (pintype "passive"))
      (node (ref "U2") (pin "2") (pinfunction "VCC_2") (pintype "power_in"))
      (node (ref "Y1") (pin "6") (pinfunction "6_6") (pintype "passive"))
    )
    (net (code "66") (name "unconnected-(U1-P4.1{slash}MISO_3-Pad29)") (class "Default")
      (node (ref "U1") (pin "29") (pinfunction "P4.1/MISO_3_29") (pintype "passive"))
    )
    (net (code "67") (name "unconnected-(U1-P5.4{slash}RST{slash}MCLKO{slash}SS_3-Pad17)") (class "Default")
      (node (ref "U1") (pin "17") (pinfunction "P5.4/RST/MCLKO/SS_3_17") (pintype "passive"))
    )
    (net (code "68") (name "unconnected-(U2-32kHz-Pad1)") (class "Default")
      (node (ref "U2") (pin "1") (pinfunction "32kHz_1") (pintype "open_collector"))
    )
    (net (code "69") (name "unconnected-(U2-~{INT}{slash}SQW-Pad3)") (class "Default")
      (node (ref "U2") (pin "3") (pinfunction "~{INT}/SQW_3") (pintype "bidirectional"))
    )
    (net (code "70") (name "unconnected-(U2-~{RST}-Pad4)") (class "Default")
      (node (ref "U2") (pin "4") (pinfunction "~{RST}_4") (pintype "bidirectional"))
    )
    (net (code "71") (name "unconnected-(Y1-Pad1)") (class "Default")
      (node (ref "Y1") (pin "1") (pinfunction "1_1") (pintype "passive"))
    )
  )
)
